# TinkerKit-board.net
KiCad netlist of a schematic drawn in EAGLE
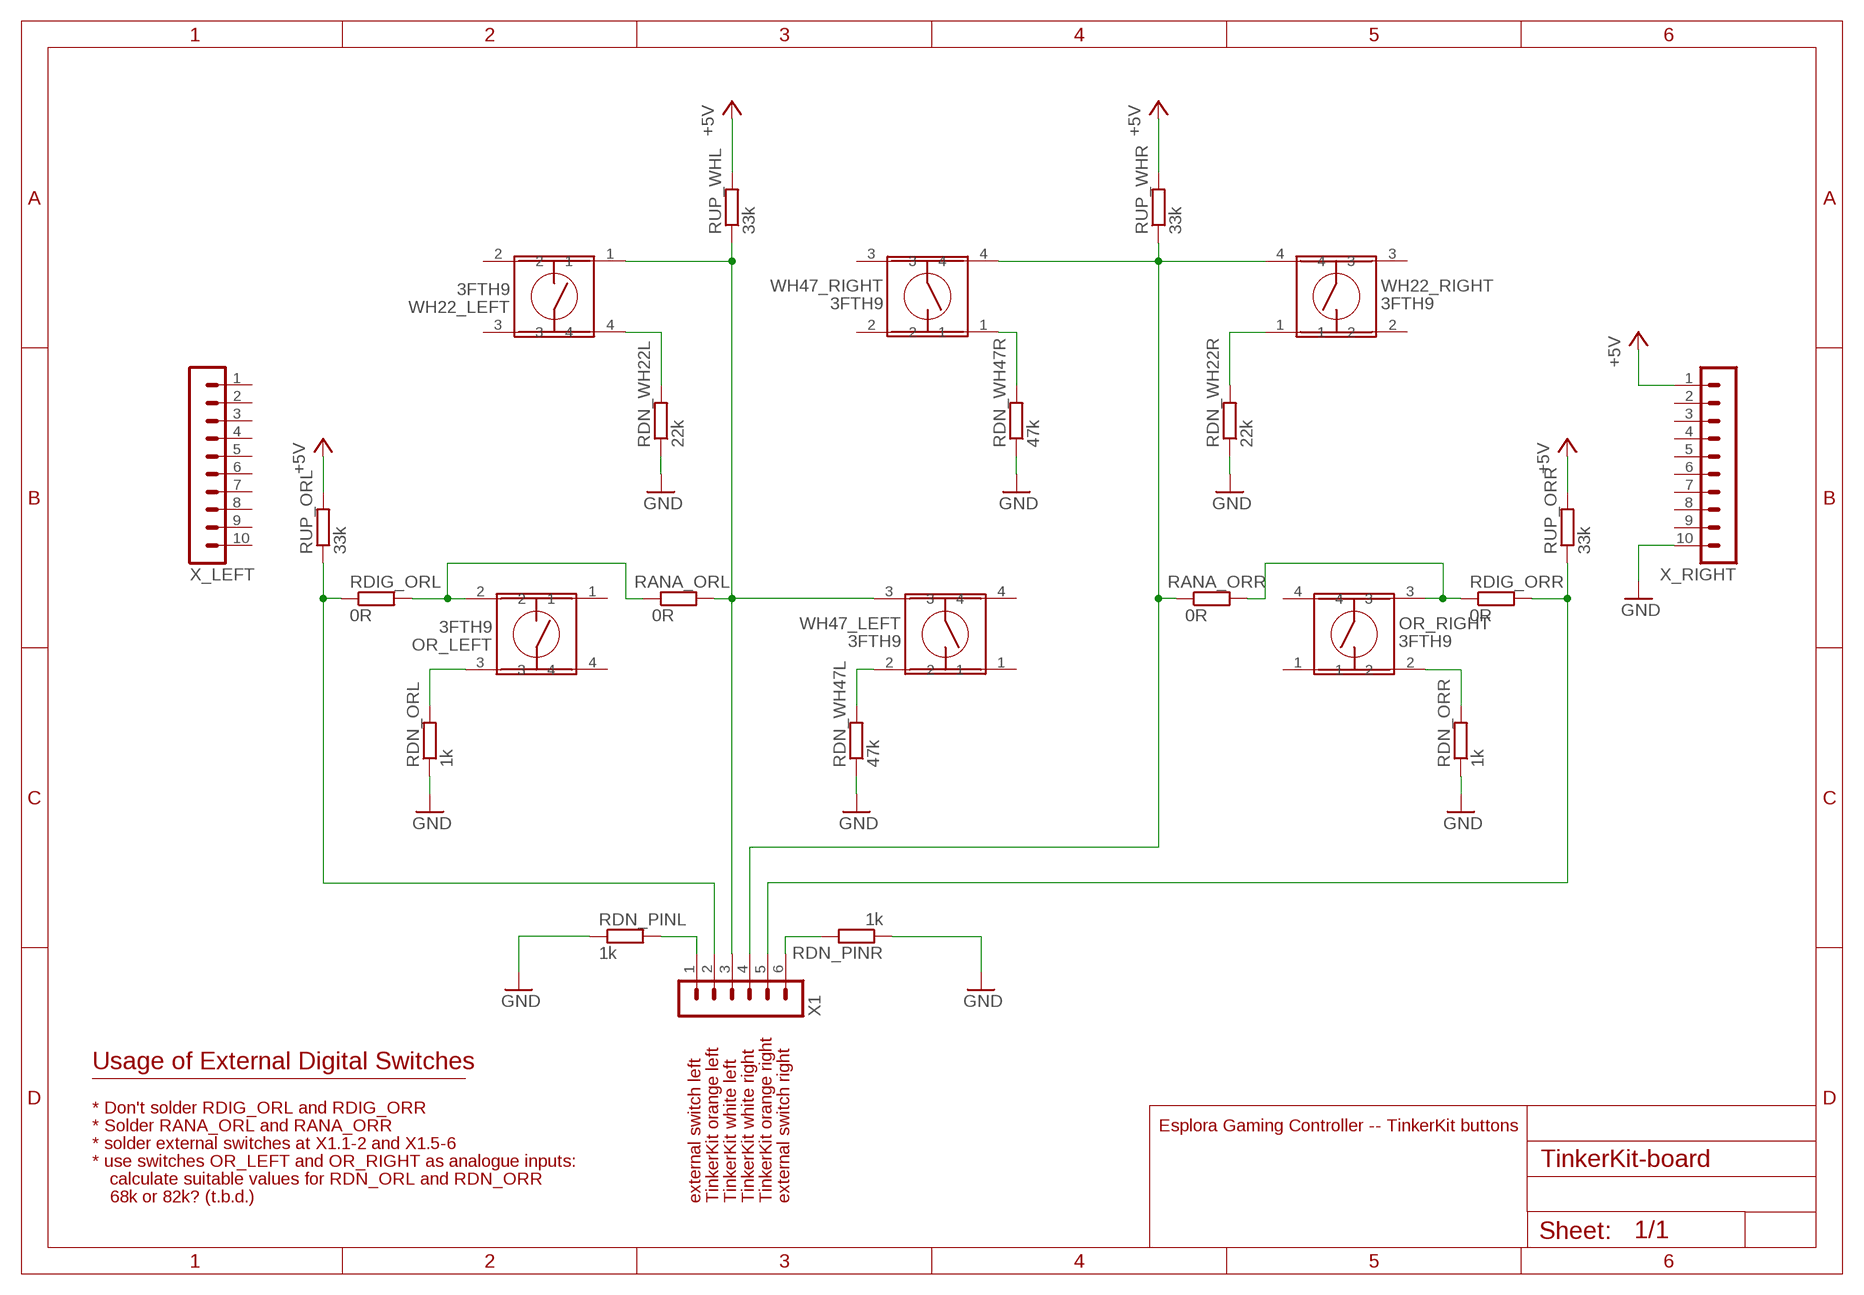
[diagram p0: schematic, sheet 1]

(export (version "E")
  (design (tool "Eeschema 10.0.6"))
  (components
    (comp (ref "OR_LEFT")
      (value "3FTH9")
      (footprint "eagle-import:3FTH9")
      (libsource (lib "eagle-import") (part "3FTH9"))
    )
    (comp (ref "OR_RIGHT")
      (value "3FTH9")
      (footprint "eagle-import:3FTH9")
      (libsource (lib "eagle-import") (part "3FTH9"))
    )
    (comp (ref "RANA_ORL")
      (value "0R")
      (footprint "eagle-import:R0603")
      (libsource (lib "eagle-import") (part "R-EU_R0603"))
    )
    (comp (ref "RANA_ORR")
      (value "0R")
      (footprint "eagle-import:R0603")
      (libsource (lib "eagle-import") (part "R-EU_R0603"))
    )
    (comp (ref "RDIG_ORL")
      (value "0R")
      (footprint "eagle-import:R0603")
      (libsource (lib "eagle-import") (part "R-EU_R0603"))
    )
    (comp (ref "RDIG_ORR")
      (value "0R")
      (footprint "eagle-import:R0603")
      (libsource (lib "eagle-import") (part "R-EU_R0603"))
    )
    (comp (ref "RDN_ORL")
      (value "1k")
      (footprint "eagle-import:M1206")
      (libsource (lib "eagle-import") (part "R-EU_M1206"))
    )
    (comp (ref "RDN_ORR")
      (value "1k")
      (footprint "eagle-import:M1206")
      (libsource (lib "eagle-import") (part "R-EU_M1206"))
    )
    (comp (ref "RDN_PINL")
      (value "1k")
      (footprint "eagle-import:R0603")
      (libsource (lib "eagle-import") (part "R-EU_R0603"))
    )
    (comp (ref "RDN_PINR")
      (value "1k")
      (footprint "eagle-import:R0603")
      (libsource (lib "eagle-import") (part "R-EU_R0603"))
    )
    (comp (ref "RDN_WH22L")
      (value "22k")
      (footprint "eagle-import:M1206")
      (libsource (lib "eagle-import") (part "R-EU_M1206"))
    )
    (comp (ref "RDN_WH22R")
      (value "22k")
      (footprint "eagle-import:M1206")
      (libsource (lib "eagle-import") (part "R-EU_M1206"))
    )
    (comp (ref "RDN_WH47L")
      (value "47k")
      (footprint "eagle-import:M1206")
      (libsource (lib "eagle-import") (part "R-EU_M1206"))
    )
    (comp (ref "RDN_WH47R")
      (value "47k")
      (footprint "eagle-import:M1206")
      (libsource (lib "eagle-import") (part "R-EU_M1206"))
    )
    (comp (ref "RUP_ORL")
      (value "33k")
      (footprint "eagle-import:M1206")
      (libsource (lib "eagle-import") (part "R-EU_M1206"))
    )
    (comp (ref "RUP_ORR")
      (value "33k")
      (footprint "eagle-import:M1206")
      (libsource (lib "eagle-import") (part "R-EU_M1206"))
    )
    (comp (ref "RUP_WHL")
      (value "33k")
      (footprint "eagle-import:M1206")
      (libsource (lib "eagle-import") (part "R-EU_M1206"))
    )
    (comp (ref "RUP_WHR")
      (value "33k")
      (footprint "eagle-import:M1206")
      (libsource (lib "eagle-import") (part "R-EU_M1206"))
    )
    (comp (ref "WH22_LEFT")
      (value "3FTH9")
      (footprint "eagle-import:3FTH9")
      (libsource (lib "eagle-import") (part "3FTH9"))
    )
    (comp (ref "WH22_RIGHT")
      (value "3FTH9")
      (footprint "eagle-import:3FTH9")
      (libsource (lib "eagle-import") (part "3FTH9"))
    )
    (comp (ref "WH47_LEFT")
      (value "3FTH9")
      (footprint "eagle-import:3FTH9")
      (libsource (lib "eagle-import") (part "3FTH9"))
    )
    (comp (ref "WH47_RIGHT")
      (value "3FTH9")
      (footprint "eagle-import:3FTH9")
      (libsource (lib "eagle-import") (part "3FTH9"))
    )
    (comp (ref "X1")
      (value "MA06-1")
      (footprint "eagle-import:MA06-1")
      (libsource (lib "eagle-import") (part "MA06-1"))
    )
    (comp (ref "X_LEFT")
      (value "MA10-1")
      (footprint "eagle-import:MA10-1")
      (libsource (lib "eagle-import") (part "MA10-1"))
    )
    (comp (ref "X_RIGHT")
      (value "MA10-1")
      (footprint "eagle-import:MA10-1")
      (libsource (lib "eagle-import") (part "MA10-1"))
    )
  )
  (nets
    (net (code "1") (name "+5V") (class "Default")
      (node (ref "RUP_ORL") (pin "2") (pinfunction "2_2") (pintype "passive"))
      (node (ref "RUP_ORR") (pin "2") (pinfunction "2_2") (pintype "passive"))
      (node (ref "RUP_WHL") (pin "2") (pinfunction "2_2") (pintype "passive"))
      (node (ref "RUP_WHR") (pin "2") (pinfunction "2_2") (pintype "passive"))
      (node (ref "X_RIGHT") (pin "1") (pinfunction "1_1") (pintype "passive"))
    )
    (net (code "2") (name "GND") (class "Default")
      (node (ref "RDN_ORL") (pin "1") (pinfunction "1_1") (pintype "passive"))
      (node (ref "RDN_ORR") (pin "1") (pinfunction "1_1") (pintype "passive"))
      (node (ref "RDN_PINL") (pin "1") (pinfunction "1_1") (pintype "passive"))
      (node (ref "RDN_PINR") (pin "1") (pinfunction "1_1") (pintype "passive"))
      (node (ref "RDN_WH22L") (pin "1") (pinfunction "1_1") (pintype "passive"))
      (node (ref "RDN_WH22R") (pin "1") (pinfunction "1_1") (pintype "passive"))
      (node (ref "RDN_WH47L") (pin "1") (pinfunction "1_1") (pintype "passive"))
      (node (ref "RDN_WH47R") (pin "1") (pinfunction "1_1") (pintype "passive"))
      (node (ref "X_RIGHT") (pin "10") (pinfunction "10_10") (pintype "passive"))
    )
    (net (code "3") (name "Net-(OR_LEFT-Pad2)") (class "Default")
      (node (ref "OR_LEFT") (pin "2") (pinfunction "2_2") (pintype "passive"))
      (node (ref "RANA_ORL") (pin "1") (pinfunction "1_1") (pintype "passive"))
      (node (ref "RDIG_ORL") (pin "2") (pinfunction "2_2") (pintype "passive"))
    )
    (net (code "4") (name "Net-(OR_LEFT-Pad3)") (class "Default")
      (node (ref "OR_LEFT") (pin "3") (pinfunction "3_3") (pintype "passive"))
      (node (ref "RDN_ORL") (pin "2") (pinfunction "2_2") (pintype "passive"))
    )
    (net (code "5") (name "Net-(OR_RIGHT-Pad2)") (class "Default")
      (node (ref "OR_RIGHT") (pin "2") (pinfunction "2_2") (pintype "passive"))
      (node (ref "RDN_ORR") (pin "2") (pinfunction "2_2") (pintype "passive"))
    )
    (net (code "6") (name "Net-(OR_RIGHT-Pad3)") (class "Default")
      (node (ref "OR_RIGHT") (pin "3") (pinfunction "3_3") (pintype "passive"))
      (node (ref "RANA_ORR") (pin "2") (pinfunction "2_2") (pintype "passive"))
      (node (ref "RDIG_ORR") (pin "1") (pinfunction "1_1") (pintype "passive"))
    )
    (net (code "7") (name "Net-(RANA_ORL-Pad2)") (class "Default")
      (node (ref "RANA_ORL") (pin "2") (pinfunction "2_2") (pintype "passive"))
      (node (ref "RUP_WHL") (pin "1") (pinfunction "1_1") (pintype "passive"))
      (node (ref "WH22_LEFT") (pin "1") (pinfunction "1_1") (pintype "passive"))
      (node (ref "WH47_LEFT") (pin "3") (pinfunction "3_3") (pintype "passive"))
      (node (ref "X1") (pin "3") (pinfunction "3_3") (pintype "passive"))
    )
    (net (code "8") (name "Net-(RANA_ORR-Pad1)") (class "Default")
      (node (ref "RANA_ORR") (pin "1") (pinfunction "1_1") (pintype "passive"))
      (node (ref "RUP_WHR") (pin "1") (pinfunction "1_1") (pintype "passive"))
      (node (ref "WH22_RIGHT") (pin "4") (pinfunction "4_4") (pintype "passive"))
      (node (ref "WH47_RIGHT") (pin "4") (pinfunction "4_4") (pintype "passive"))
      (node (ref "X1") (pin "4") (pinfunction "4_4") (pintype "passive"))
    )
    (net (code "9") (name "Net-(RDIG_ORL-Pad1)") (class "Default")
      (node (ref "RDIG_ORL") (pin "1") (pinfunction "1_1") (pintype "passive"))
      (node (ref "RUP_ORL") (pin "1") (pinfunction "1_1") (pintype "passive"))
      (node (ref "X1") (pin "2") (pinfunction "2_2") (pintype "passive"))
    )
    (net (code "10") (name "Net-(RDIG_ORR-Pad2)") (class "Default")
      (node (ref "RDIG_ORR") (pin "2") (pinfunction "2_2") (pintype "passive"))
      (node (ref "RUP_ORR") (pin "1") (pinfunction "1_1") (pintype "passive"))
      (node (ref "X1") (pin "5") (pinfunction "5_5") (pintype "passive"))
    )
    (net (code "11") (name "Net-(RDN_PINL-Pad2)") (class "Default")
      (node (ref "RDN_PINL") (pin "2") (pinfunction "2_2") (pintype "passive"))
      (node (ref "X1") (pin "1") (pinfunction "1_1") (pintype "passive"))
    )
    (net (code "12") (name "Net-(RDN_PINR-Pad2)") (class "Default")
      (node (ref "RDN_PINR") (pin "2") (pinfunction "2_2") (pintype "passive"))
      (node (ref "X1") (pin "6") (pinfunction "6_6") (pintype "passive"))
    )
    (net (code "13") (name "Net-(RDN_WH22L-Pad2)") (class "Default")
      (node (ref "RDN_WH22L") (pin "2") (pinfunction "2_2") (pintype "passive"))
      (node (ref "WH22_LEFT") (pin "4") (pinfunction "4_4") (pintype "passive"))
    )
    (net (code "14") (name "Net-(RDN_WH22R-Pad2)") (class "Default")
      (node (ref "RDN_WH22R") (pin "2") (pinfunction "2_2") (pintype "passive"))
      (node (ref "WH22_RIGHT") (pin "1") (pinfunction "1_1") (pintype "passive"))
    )
    (net (code "15") (name "Net-(RDN_WH47L-Pad2)") (class "Default")
      (node (ref "RDN_WH47L") (pin "2") (pinfunction "2_2") (pintype "passive"))
      (node (ref "WH47_LEFT") (pin "2") (pinfunction "2_2") (pintype "passive"))
    )
    (net (code "16") (name "Net-(RDN_WH47R-Pad2)") (class "Default")
      (node (ref "RDN_WH47R") (pin "2") (pinfunction "2_2") (pintype "passive"))
      (node (ref "WH47_RIGHT") (pin "1") (pinfunction "1_1") (pintype "passive"))
    )
    (net (code "17") (name "unconnected-(OR_LEFT-Pad1)") (class "Default")
      (node (ref "OR_LEFT") (pin "1") (pinfunction "1_1") (pintype "passive"))
    )
    (net (code "18") (name "unconnected-(OR_LEFT-Pad4)") (class "Default")
      (node (ref "OR_LEFT") (pin "4") (pinfunction "4_4") (pintype "passive"))
    )
    (net (code "19") (name "unconnected-(OR_RIGHT-Pad1)") (class "Default")
      (node (ref "OR_RIGHT") (pin "1") (pinfunction "1_1") (pintype "passive"))
    )
    (net (code "20") (name "unconnected-(OR_RIGHT-Pad4)") (class "Default")
      (node (ref "OR_RIGHT") (pin "4") (pinfunction "4_4") (pintype "passive"))
    )
    (net (code "21") (name "unconnected-(WH22_LEFT-Pad2)") (class "Default")
      (node (ref "WH22_LEFT") (pin "2") (pinfunction "2_2") (pintype "passive"))
    )
    (net (code "22") (name "unconnected-(WH22_LEFT-Pad3)") (class "Default")
      (node (ref "WH22_LEFT") (pin "3") (pinfunction "3_3") (pintype "passive"))
    )
    (net (code "23") (name "unconnected-(WH22_RIGHT-Pad2)") (class "Default")
      (node (ref "WH22_RIGHT") (pin "2") (pinfunction "2_2") (pintype "passive"))
    )
    (net (code "24") (name "unconnected-(WH22_RIGHT-Pad3)") (class "Default")
      (node (ref "WH22_RIGHT") (pin "3") (pinfunction "3_3") (pintype "passive"))
    )
    (net (code "25") (name "unconnected-(WH47_LEFT-Pad1)") (class "Default")
      (node (ref "WH47_LEFT") (pin "1") (pinfunction "1_1") (pintype "passive"))
    )
    (net (code "26") (name "unconnected-(WH47_LEFT-Pad4)") (class "Default")
      (node (ref "WH47_LEFT") (pin "4") (pinfunction "4_4") (pintype "passive"))
    )
    (net (code "27") (name "unconnected-(WH47_RIGHT-Pad2)") (class "Default")
      (node (ref "WH47_RIGHT") (pin "2") (pinfunction "2_2") (pintype "passive"))
    )
    (net (code "28") (name "unconnected-(WH47_RIGHT-Pad3)") (class "Default")
      (node (ref "WH47_RIGHT") (pin "3") (pinfunction "3_3") (pintype "passive"))
    )
    (net (code "29") (name "unconnected-(X_LEFT-Pad1)") (class "Default")
      (node (ref "X_LEFT") (pin "1") (pinfunction "1_1") (pintype "passive"))
    )
    (net (code "30") (name "unconnected-(X_LEFT-Pad2)") (class "Default")
      (node (ref "X_LEFT") (pin "2") (pinfunction "2_2") (pintype "passive"))
    )
    (net (code "31") (name "unconnected-(X_LEFT-Pad3)") (class "Default")
      (node (ref "X_LEFT") (pin "3") (pinfunction "3_3") (pintype "passive"))
    )
    (net (code "32") (name "unconnected-(X_LEFT-Pad4)") (class "Default")
      (node (ref "X_LEFT") (pin "4") (pinfunction "4_4") (pintype "passive"))
    )
    (net (code "33") (name "unconnected-(X_LEFT-Pad5)") (class "Default")
      (node (ref "X_LEFT") (pin "5") (pinfunction "5_5") (pintype "passive"))
    )
    (net (code "34") (name "unconnected-(X_LEFT-Pad6)") (class "Default")
      (node (ref "X_LEFT") (pin "6") (pinfunction "6_6") (pintype "passive"))
    )
    (net (code "35") (name "unconnected-(X_LEFT-Pad7)") (class "Default")
      (node (ref "X_LEFT") (pin "7") (pinfunction "7_7") (pintype "passive"))
    )
    (net (code "36") (name "unconnected-(X_LEFT-Pad8)") (class "Default")
      (node (ref "X_LEFT") (pin "8") (pinfunction "8_8") (pintype "passive"))
    )
    (net (code "37") (name "unconnected-(X_LEFT-Pad9)") (class "Default")
      (node (ref "X_LEFT") (pin "9") (pinfunction "9_9") (pintype "passive"))
    )
    (net (code "38") (name "unconnected-(X_LEFT-Pad10)") (class "Default")
      (node (ref "X_LEFT") (pin "10") (pinfunction "10_10") (pintype "passive"))
    )
    (net (code "39") (name "unconnected-(X_RIGHT-Pad2)") (class "Default")
      (node (ref "X_RIGHT") (pin "2") (pinfunction "2_2") (pintype "passive"))
    )
    (net (code "40") (name "unconnected-(X_RIGHT-Pad3)") (class "Default")
      (node (ref "X_RIGHT") (pin "3") (pinfunction "3_3") (pintype "passive"))
    )
    (net (code "41") (name "unconnected-(X_RIGHT-Pad4)") (class "Default")
      (node (ref "X_RIGHT") (pin "4") (pinfunction "4_4") (pintype "passive"))
    )
    (net (code "42") (name "unconnected-(X_RIGHT-Pad5)") (class "Default")
      (node (ref "X_RIGHT") (pin "5") (pinfunction "5_5") (pintype "passive"))
    )
    (net (code "43") (name "unconnected-(X_RIGHT-Pad6)") (class "Default")
      (node (ref "X_RIGHT") (pin "6") (pinfunction "6_6") (pintype "passive"))
    )
    (net (code "44") (name "unconnected-(X_RIGHT-Pad7)") (class "Default")
      (node (ref "X_RIGHT") (pin "7") (pinfunction "7_7") (pintype "passive"))
    )
    (net (code "45") (name "unconnected-(X_RIGHT-Pad8)") (class "Default")
      (node (ref "X_RIGHT") (pin "8") (pinfunction "8_8") (pintype "passive"))
    )
    (net (code "46") (name "unconnected-(X_RIGHT-Pad9)") (class "Default")
      (node (ref "X_RIGHT") (pin "9") (pinfunction "9_9") (pintype "passive"))
    )
  )
)
